# v1_circuit_EAGLE.net
KiCad netlist of a schematic drawn in EAGLE
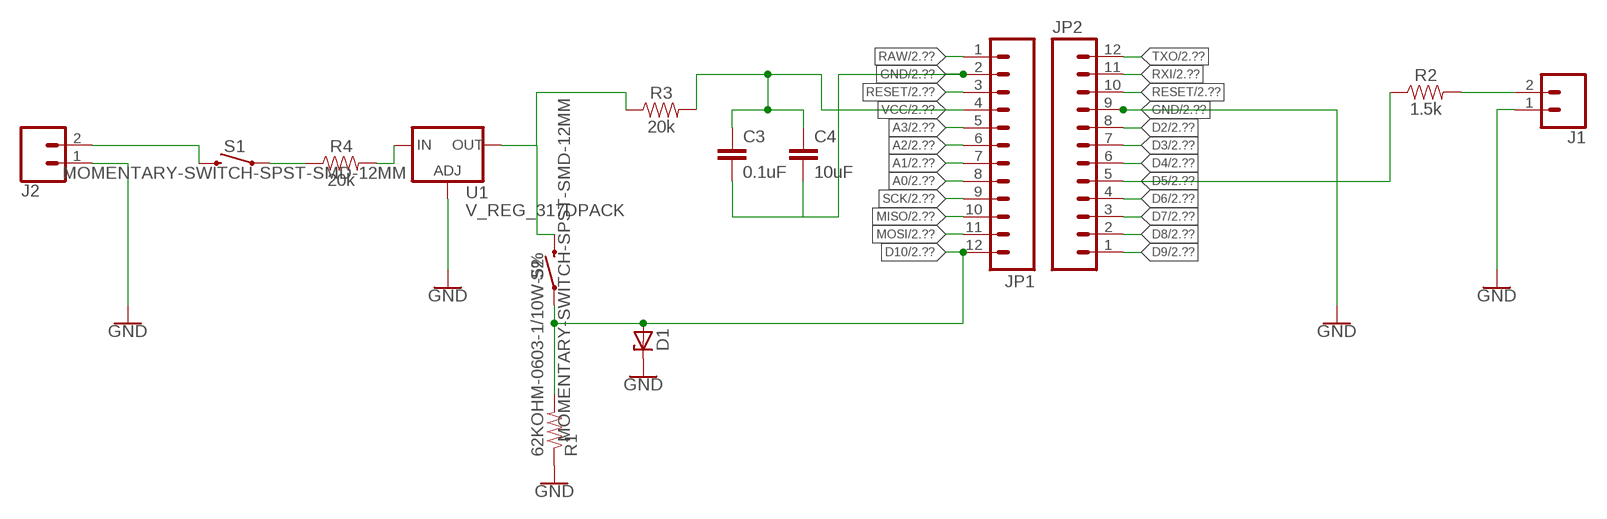
[diagram p0: schematic, sheet 1]
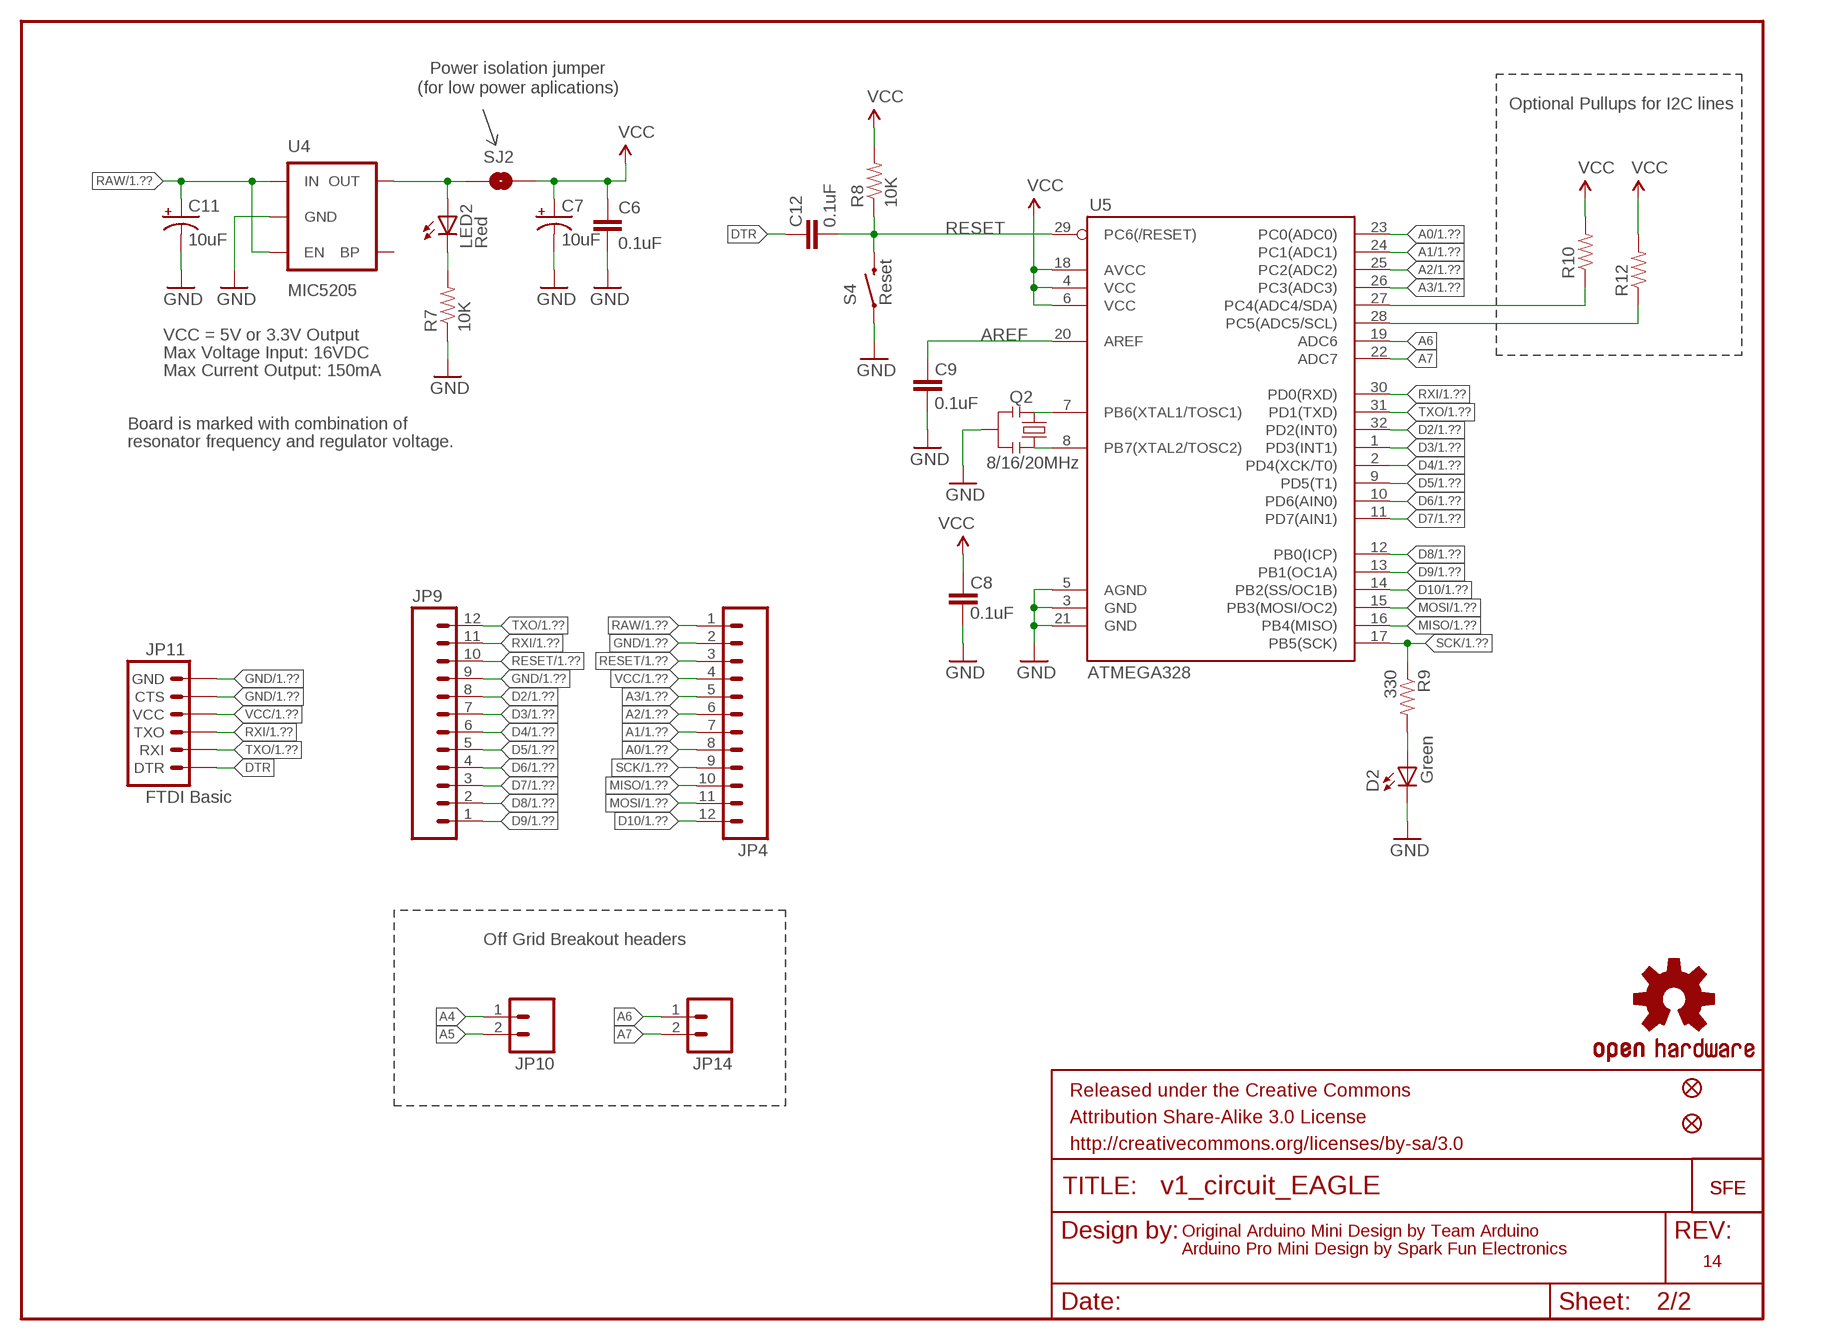
[diagram p1: schematic, sheet 2]

(export (version "E")
  (design (tool "Eeschema 10.0.6"))
  (components
    (comp (ref "C3")
      (value "0.1uF")
      (footprint "eagle-import:0603")
      (libsource (lib "eagle-import") (part "0.1UF-0603-100V-10%"))
    )
    (comp (ref "C4")
      (value "10uF")
      (footprint "eagle-import:0805")
      (libsource (lib "eagle-import") (part "10UF-0805-10V-10%"))
    )
    (comp (ref "D1")
      (value "ZENER-DIODETO236")
      (footprint "eagle-import:TO236")
      (libsource (lib "eagle-import") (part "ZENER-DIODETO236"))
    )
    (comp (ref "J1")
      (value "CONN_02-JST-2MM-SMT")
      (footprint "eagle-import:JST-2-SMD")
      (libsource (lib "eagle-import") (part "CONN_02-JST-2MM-SMT"))
    )
    (comp (ref "J2")
      (value "CONN_02-JST-2MM-SMT")
      (footprint "eagle-import:JST-2-SMD")
      (libsource (lib "eagle-import") (part "CONN_02-JST-2MM-SMT"))
    )
    (comp (ref "JP1")
      (value "M12PTH")
      (footprint "eagle-import:1X12")
      (libsource (lib "eagle-import") (part "M12PTH"))
    )
    (comp (ref "JP2")
      (value "M12PTH")
      (footprint "eagle-import:1X12")
      (libsource (lib "eagle-import") (part "M12PTH"))
    )
    (comp (ref "R1")
      (value "62KOHM-0603-1/10W-5%")
      (footprint "eagle-import:0603")
      (libsource (lib "eagle-import") (part "62KOHM-0603-1/10W-5%"))
    )
    (comp (ref "R2")
      (value "1.5k")
      (footprint "eagle-import:0603")
      (libsource (lib "eagle-import") (part "1.5KOHM-0603-1/10W-1%"))
    )
    (comp (ref "R3")
      (value "20k")
      (footprint "eagle-import:0603")
      (libsource (lib "eagle-import") (part "20KOHM-0603-1/10W-5%"))
    )
    (comp (ref "R4")
      (value "20k")
      (footprint "eagle-import:0603")
      (libsource (lib "eagle-import") (part "20KOHM-0603-1/10W-5%"))
    )
    (comp (ref "S1")
      (value "MOMENTARY-SWITCH-SPST-SMD-12MM")
      (footprint "eagle-import:TACTILE_SWITCH_SMD_12MM")
      (libsource (lib "eagle-import") (part "MOMENTARY-SWITCH-SPST-SMD-12MM"))
    )
    (comp (ref "S2")
      (value "MOMENTARY-SWITCH-SPST-SMD-12MM")
      (footprint "eagle-import:TACTILE_SWITCH_SMD_12MM")
      (libsource (lib "eagle-import") (part "MOMENTARY-SWITCH-SPST-SMD-12MM"))
    )
    (comp (ref "U1")
      (value "V_REG_317DPACK")
      (footprint "eagle-import:V-REG_DPACK")
      (libsource (lib "eagle-import") (part "V_REG_317DPACK"))
    )
    (comp (ref "C6")
      (value "0.1uF")
      (footprint "eagle-import:0603-CAP")
      (libsource (lib "eagle-import") (part "CAP0603-CAP"))
    )
    (comp (ref "C7")
      (value "10uF")
      (footprint "eagle-import:EIA3216")
      (libsource (lib "eagle-import") (part "CAP_POL1206"))
    )
    (comp (ref "C8")
      (value "0.1uF")
      (footprint "eagle-import:0603-CAP")
      (libsource (lib "eagle-import") (part "CAP0603-CAP"))
    )
    (comp (ref "C9")
      (value "0.1uF")
      (footprint "eagle-import:0603-CAP")
      (libsource (lib "eagle-import") (part "CAP0603-CAP"))
    )
    (comp (ref "C11")
      (value "10uF")
      (footprint "eagle-import:EIA3216")
      (libsource (lib "eagle-import") (part "CAP_POL1206"))
    )
    (comp (ref "C12")
      (value "0.1uF")
      (footprint "eagle-import:0603-CAP")
      (libsource (lib "eagle-import") (part "CAP0603-CAP"))
    )
    (comp (ref "D2")
      (value "Green")
      (footprint "eagle-import:0603-LED-ALT1")
      (libsource (lib "eagle-import") (part "LED"))
    )
    (comp (ref "FRAME2")
      (value "FRAME-LETTER")
      (footprint "eagle-import:CREATIVE_COMMONS")
      (libsource (lib "eagle-import") (part "FRAME-LETTER"))
    )
    (comp (ref "JP4")
      (value "M12PTH")
      (footprint "eagle-import:1X12")
      (libsource (lib "eagle-import") (part "M12PTH"))
    )
    (comp (ref "JP9")
      (value "M12PTH")
      (footprint "eagle-import:1X12")
      (libsource (lib "eagle-import") (part "M12PTH"))
    )
    (comp (ref "JP10")
      (value "M02PTH")
      (footprint "eagle-import:1X02")
      (libsource (lib "eagle-import") (part "M02PTH"))
    )
    (comp (ref "JP11")
      (value "FTDI Basic")
      (footprint "eagle-import:1X06")
      (libsource (lib "eagle-import") (part "ARDUINO_SERIAL_PROGRAMPTH"))
    )
    (comp (ref "JP12")
      (value "FIDUCIALUFIDUCIAL")
      (footprint "eagle-import:MICRO-FIDUCIAL")
      (libsource (lib "eagle-import") (part "FIDUCIALUFIDUCIAL"))
    )
    (comp (ref "JP13")
      (value "FIDUCIALUFIDUCIAL")
      (footprint "eagle-import:MICRO-FIDUCIAL")
      (libsource (lib "eagle-import") (part "FIDUCIALUFIDUCIAL"))
    )
    (comp (ref "JP14")
      (value "M02PTH")
      (footprint "eagle-import:1X02")
      (libsource (lib "eagle-import") (part "M02PTH"))
    )
    (comp (ref "LED2")
      (value "Red")
      (footprint "eagle-import:0603-LED-ALT1")
      (libsource (lib "eagle-import") (part "LED"))
    )
    (comp (ref "Q2")
      (value "8/16/20MHz")
      (footprint "eagle-import:RESONATOR-SMD-1_1")
      (libsource (lib "eagle-import") (part "RESONATOR1{colon}1"))
    )
    (comp (ref "R7")
      (value "10K")
      (footprint "eagle-import:0603-RES")
      (libsource (lib "eagle-import") (part "RESISTOR0603-RES"))
    )
    (comp (ref "R8")
      (value "10K")
      (footprint "eagle-import:0603-RES")
      (libsource (lib "eagle-import") (part "RESISTOR0603-RES"))
    )
    (comp (ref "R9")
      (value "330")
      (footprint "eagle-import:0603-RES")
      (libsource (lib "eagle-import") (part "RESISTOR0603-RES"))
    )
    (comp (ref "R10")
      (value "RESISTOR0603-RES")
      (footprint "eagle-import:0603-RES")
      (libsource (lib "eagle-import") (part "RESISTOR0603-RES"))
    )
    (comp (ref "R12")
      (value "RESISTOR0603-RES")
      (footprint "eagle-import:0603-RES")
      (libsource (lib "eagle-import") (part "RESISTOR0603-RES"))
    )
    (comp (ref "S4")
      (value "Reset")
      (footprint "eagle-import:TACTILE-SWITCH-SMD-ALT01")
      (libsource (lib "eagle-import") (part "SWITCH-MOMENTARY-2SMD-ALT01"))
    )
    (comp (ref "SJ2")
      (value "SOLDERJUMPERNC")
      (footprint "eagle-import:SJ_2S")
      (libsource (lib "eagle-import") (part "SOLDERJUMPERNC"))
    )
    (comp (ref "U$2")
      (value "LOGO-SFENEW")
      (footprint "eagle-import:SFE-NEW-WEBLOGO")
      (libsource (lib "eagle-import") (part "LOGO-SFENEW"))
    )
    (comp (ref "U$4")
      (value "LOGO-SFESK")
      (footprint "eagle-import:SFE-LOGO-FLAME")
      (libsource (lib "eagle-import") (part "LOGO-SFESK"))
    )
    (comp (ref "U$5")
      (value "OSHW-LOGOS")
      (footprint "eagle-import:OSHW-LOGO-S")
      (libsource (lib "eagle-import") (part "OSHW-LOGOS"))
    )
    (comp (ref "U4")
      (value "MIC5205")
      (footprint "eagle-import:SOT23-5")
      (libsource (lib "eagle-import") (part "V_REG_LDOSMD"))
    )
    (comp (ref "U5")
      (value "ATMEGA328")
      (footprint "eagle-import:TQFP32-08")
      (libsource (lib "eagle-import") (part "ATMEGA168"))
    )
  )
  (nets
    (net (code "1") (name "A0") (class "Default")
      (node (ref "JP1") (pin "8") (pinfunction "8_8") (pintype "passive"))
      (node (ref "JP4") (pin "8") (pinfunction "8_8") (pintype "passive"))
      (node (ref "U5") (pin "23") (pinfunction "PC0(ADC0)_23") (pintype "bidirectional"))
    )
    (net (code "2") (name "A1") (class "Default")
      (node (ref "JP1") (pin "7") (pinfunction "7_7") (pintype "passive"))
      (node (ref "JP4") (pin "7") (pinfunction "7_7") (pintype "passive"))
      (node (ref "U5") (pin "24") (pinfunction "PC1(ADC1)_24") (pintype "bidirectional"))
    )
    (net (code "3") (name "A2") (class "Default")
      (node (ref "JP1") (pin "6") (pinfunction "6_6") (pintype "passive"))
      (node (ref "JP4") (pin "6") (pinfunction "6_6") (pintype "passive"))
      (node (ref "U5") (pin "25") (pinfunction "PC2(ADC2)_25") (pintype "bidirectional"))
    )
    (net (code "4") (name "A3") (class "Default")
      (node (ref "JP1") (pin "5") (pinfunction "5_5") (pintype "passive"))
      (node (ref "JP4") (pin "5") (pinfunction "5_5") (pintype "passive"))
      (node (ref "U5") (pin "26") (pinfunction "PC3(ADC3)_26") (pintype "bidirectional"))
    )
    (net (code "5") (name "A4") (class "Default")
      (node (ref "JP10") (pin "1") (pinfunction "1_1") (pintype "passive"))
      (node (ref "R10") (pin "1") (pinfunction "1_1") (pintype "passive"))
      (node (ref "U5") (pin "27") (pinfunction "PC4(ADC4/SDA)_27") (pintype "bidirectional"))
    )
    (net (code "6") (name "A5") (class "Default")
      (node (ref "JP10") (pin "2") (pinfunction "2_2") (pintype "passive"))
      (node (ref "R12") (pin "1") (pinfunction "1_1") (pintype "passive"))
      (node (ref "U5") (pin "28") (pinfunction "PC5(ADC5/SCL)_28") (pintype "bidirectional"))
    )
    (net (code "7") (name "A6") (class "Default")
      (node (ref "JP14") (pin "1") (pinfunction "1_1") (pintype "passive"))
      (node (ref "U5") (pin "19") (pinfunction "ADC6_19") (pintype "bidirectional"))
    )
    (net (code "8") (name "A7") (class "Default")
      (node (ref "JP14") (pin "2") (pinfunction "2_2") (pintype "passive"))
      (node (ref "U5") (pin "22") (pinfunction "ADC7_22") (pintype "bidirectional"))
    )
    (net (code "9") (name "AREF") (class "Default")
      (node (ref "C9") (pin "2") (pinfunction "2_2") (pintype "passive"))
      (node (ref "U5") (pin "20") (pinfunction "AREF_20") (pintype "bidirectional"))
    )
    (net (code "10") (name "D2") (class "Default")
      (node (ref "JP2") (pin "8") (pinfunction "8_8") (pintype "passive"))
      (node (ref "JP9") (pin "8") (pinfunction "8_8") (pintype "passive"))
      (node (ref "U5") (pin "32") (pinfunction "PD2(INT0)_32") (pintype "bidirectional"))
    )
    (net (code "11") (name "D3") (class "Default")
      (node (ref "JP2") (pin "7") (pinfunction "7_7") (pintype "passive"))
      (node (ref "JP9") (pin "7") (pinfunction "7_7") (pintype "passive"))
      (node (ref "U5") (pin "1") (pinfunction "PD3(INT1)_1") (pintype "bidirectional"))
    )
    (net (code "12") (name "D4") (class "Default")
      (node (ref "JP2") (pin "6") (pinfunction "6_6") (pintype "passive"))
      (node (ref "JP9") (pin "6") (pinfunction "6_6") (pintype "passive"))
      (node (ref "U5") (pin "2") (pinfunction "PD4(XCK/T0)_2") (pintype "bidirectional"))
    )
    (net (code "13") (name "D5") (class "Default")
      (node (ref "JP2") (pin "5") (pinfunction "5_5") (pintype "passive"))
      (node (ref "JP9") (pin "5") (pinfunction "5_5") (pintype "passive"))
      (node (ref "R2") (pin "1") (pinfunction "1_1") (pintype "passive"))
      (node (ref "U5") (pin "9") (pinfunction "PD5(T1)_9") (pintype "bidirectional"))
    )
    (net (code "14") (name "D6") (class "Default")
      (node (ref "JP2") (pin "4") (pinfunction "4_4") (pintype "passive"))
      (node (ref "JP9") (pin "4") (pinfunction "4_4") (pintype "passive"))
      (node (ref "U5") (pin "10") (pinfunction "PD6(AIN0)_10") (pintype "bidirectional"))
    )
    (net (code "15") (name "D7") (class "Default")
      (node (ref "JP2") (pin "3") (pinfunction "3_3") (pintype "passive"))
      (node (ref "JP9") (pin "3") (pinfunction "3_3") (pintype "passive"))
      (node (ref "U5") (pin "11") (pinfunction "PD7(AIN1)_11") (pintype "bidirectional"))
    )
    (net (code "16") (name "D8") (class "Default")
      (node (ref "JP2") (pin "2") (pinfunction "2_2") (pintype "passive"))
      (node (ref "JP9") (pin "2") (pinfunction "2_2") (pintype "passive"))
      (node (ref "U5") (pin "12") (pinfunction "PB0(ICP)_12") (pintype "bidirectional"))
    )
    (net (code "17") (name "D9") (class "Default")
      (node (ref "JP2") (pin "1") (pinfunction "1_1") (pintype "passive"))
      (node (ref "JP9") (pin "1") (pinfunction "1_1") (pintype "passive"))
      (node (ref "U5") (pin "13") (pinfunction "PB1(OC1A)_13") (pintype "bidirectional"))
    )
    (net (code "18") (name "D10") (class "Default")
      (node (ref "D1") (pin "A") (pinfunction "A_A") (pintype "passive"))
      (node (ref "JP1") (pin "12") (pinfunction "12_12") (pintype "passive"))
      (node (ref "JP4") (pin "12") (pinfunction "12_12") (pintype "passive"))
      (node (ref "R1") (pin "2") (pinfunction "2_2") (pintype "passive"))
      (node (ref "S2") (pin "1") (pinfunction "1_1") (pintype "passive"))
      (node (ref "U5") (pin "14") (pinfunction "PB2(SS/OC1B)_14") (pintype "bidirectional"))
    )
    (net (code "19") (name "DTR") (class "Default")
      (node (ref "C12") (pin "2") (pinfunction "2_2") (pintype "passive"))
      (node (ref "JP11") (pin "1") (pinfunction "DTR_1") (pintype "passive"))
    )
    (net (code "20") (name "GND") (class "Default")
      (node (ref "C11") (pin "C") (pinfunction "-_C") (pintype "passive"))
      (node (ref "C3") (pin "2") (pinfunction "2_2") (pintype "passive"))
      (node (ref "C4") (pin "2") (pinfunction "2_2") (pintype "passive"))
      (node (ref "C6") (pin "2") (pinfunction "2_2") (pintype "passive"))
      (node (ref "C7") (pin "C") (pinfunction "-_C") (pintype "passive"))
      (node (ref "C8") (pin "1") (pinfunction "1_1") (pintype "passive"))
      (node (ref "C9") (pin "1") (pinfunction "1_1") (pintype "passive"))
      (node (ref "D1") (pin "C") (pinfunction "C_C") (pintype "passive"))
      (node (ref "D2") (pin "C") (pinfunction "C_C") (pintype "passive"))
      (node (ref "J1") (pin "1") (pinfunction "2_1") (pintype "passive"))
      (node (ref "J2") (pin "1") (pinfunction "2_1") (pintype "passive"))
      (node (ref "JP1") (pin "2") (pinfunction "2_2") (pintype "passive"))
      (node (ref "JP11") (pin "5") (pinfunction "CTS_5") (pintype "passive"))
      (node (ref "JP11") (pin "6") (pinfunction "GND_6") (pintype "passive"))
      (node (ref "JP2") (pin "9") (pinfunction "9_9") (pintype "passive"))
      (node (ref "JP4") (pin "2") (pinfunction "2_2") (pintype "passive"))
      (node (ref "JP9") (pin "9") (pinfunction "9_9") (pintype "passive"))
      (node (ref "Q2") (pin "2") (pinfunction "2_2") (pintype "passive"))
      (node (ref "R1") (pin "1") (pinfunction "1_1") (pintype "passive"))
      (node (ref "R7") (pin "1") (pinfunction "1_1") (pintype "passive"))
      (node (ref "S4") (pin "1") (pinfunction "1_1") (pintype "passive"))
      (node (ref "S4") (pin "2") (pinfunction "1_2") (pintype "passive"))
      (node (ref "U1") (pin "1") (pinfunction "ADJ_1") (pintype "input"))
      (node (ref "U4") (pin "2") (pinfunction "GND_2") (pintype "input"))
      (node (ref "U5") (pin "21") (pinfunction "GND_21") (pintype "bidirectional"))
      (node (ref "U5") (pin "3") (pinfunction "GND_3") (pintype "bidirectional"))
      (node (ref "U5") (pin "5") (pinfunction "AGND_5") (pintype "bidirectional"))
    )
    (net (code "21") (name "MISO") (class "Default")
      (node (ref "JP1") (pin "10") (pinfunction "10_10") (pintype "passive"))
      (node (ref "JP4") (pin "10") (pinfunction "10_10") (pintype "passive"))
      (node (ref "U5") (pin "16") (pinfunction "PB4(MISO)_16") (pintype "bidirectional"))
    )
    (net (code "22") (name "MOSI") (class "Default")
      (node (ref "JP1") (pin "11") (pinfunction "11_11") (pintype "passive"))
      (node (ref "JP4") (pin "11") (pinfunction "11_11") (pintype "passive"))
      (node (ref "U5") (pin "15") (pinfunction "PB3(MOSI/OC2)_15") (pintype "bidirectional"))
    )
    (net (code "23") (name "Net-(D2-PadA)") (class "Default")
      (node (ref "D2") (pin "A") (pinfunction "A_A") (pintype "passive"))
      (node (ref "R9") (pin "2") (pinfunction "2_2") (pintype "passive"))
    )
    (net (code "24") (name "Net-(J1-1)") (class "Default")
      (node (ref "J1") (pin "2") (pinfunction "1_2") (pintype "passive"))
      (node (ref "R2") (pin "2") (pinfunction "2_2") (pintype "passive"))
    )
    (net (code "25") (name "Net-(J2-1)") (class "Default")
      (node (ref "J2") (pin "2") (pinfunction "1_2") (pintype "passive"))
      (node (ref "S1") (pin "3") (pinfunction "2_3") (pintype "passive"))
    )
    (net (code "26") (name "Net-(LED2-PadC)") (class "Default")
      (node (ref "LED2") (pin "C") (pinfunction "C_C") (pintype "passive"))
      (node (ref "R7") (pin "2") (pinfunction "2_2") (pintype "passive"))
    )
    (net (code "27") (name "Net-(R4-Pad1)") (class "Default")
      (node (ref "R4") (pin "1") (pinfunction "1_1") (pintype "passive"))
      (node (ref "S1") (pin "1") (pinfunction "1_1") (pintype "passive"))
    )
    (net (code "28") (name "Net-(S2-2)") (class "Default")
      (node (ref "R3") (pin "1") (pinfunction "1_1") (pintype "passive"))
      (node (ref "S2") (pin "3") (pinfunction "2_3") (pintype "passive"))
      (node (ref "U1") (pin "4") (pinfunction "OUT_4") (pintype "output"))
    )
    (net (code "29") (name "Net-(U1-IN)") (class "Default")
      (node (ref "R4") (pin "2") (pinfunction "2_2") (pintype "passive"))
      (node (ref "U1") (pin "3") (pinfunction "IN_3") (pintype "input"))
    )
    (net (code "30") (name "Net-(U4-OUT)") (class "Default")
      (node (ref "LED2") (pin "A") (pinfunction "A_A") (pintype "passive"))
      (node (ref "SJ2") (pin "1") (pinfunction "1_1") (pintype "passive"))
      (node (ref "U4") (pin "5") (pinfunction "OUT_5") (pintype "passive"))
    )
    (net (code "31") (name "Net-(U5-PB6(XTAL1{slash}TOSC1))") (class "Default")
      (node (ref "Q2") (pin "1") (pinfunction "1_1") (pintype "passive"))
      (node (ref "U5") (pin "7") (pinfunction "PB6(XTAL1/TOSC1)_7") (pintype "bidirectional"))
    )
    (net (code "32") (name "Net-(U5-PB7(XTAL2{slash}TOSC2))") (class "Default")
      (node (ref "Q2") (pin "3") (pinfunction "3_3") (pintype "passive"))
      (node (ref "U5") (pin "8") (pinfunction "PB7(XTAL2/TOSC2)_8") (pintype "bidirectional"))
    )
    (net (code "33") (name "RAW") (class "Default")
      (node (ref "C11") (pin "A") (pinfunction "+_A") (pintype "passive"))
      (node (ref "JP1") (pin "1") (pinfunction "1_1") (pintype "passive"))
      (node (ref "JP4") (pin "1") (pinfunction "1_1") (pintype "passive"))
      (node (ref "U4") (pin "1") (pinfunction "IN_1") (pintype "input"))
      (node (ref "U4") (pin "3") (pinfunction "EN_3") (pintype "input"))
    )
    (net (code "34") (name "RESET") (class "Default")
      (node (ref "C12") (pin "1") (pinfunction "1_1") (pintype "passive"))
      (node (ref "JP1") (pin "3") (pinfunction "3_3") (pintype "passive"))
      (node (ref "JP2") (pin "10") (pinfunction "10_10") (pintype "passive"))
      (node (ref "JP4") (pin "3") (pinfunction "3_3") (pintype "passive"))
      (node (ref "JP9") (pin "10") (pinfunction "10_10") (pintype "passive"))
      (node (ref "R8") (pin "1") (pinfunction "1_1") (pintype "passive"))
      (node (ref "S4") (pin "3") (pinfunction "2_3") (pintype "passive"))
      (node (ref "S4") (pin "4") (pinfunction "2_4") (pintype "passive"))
      (node (ref "U5") (pin "29") (pinfunction "PC6(/RESET)_29") (pintype "bidirectional"))
    )
    (net (code "35") (name "RXI") (class "Default")
      (node (ref "JP11") (pin "3") (pinfunction "TXO_3") (pintype "passive"))
      (node (ref "JP2") (pin "11") (pinfunction "11_11") (pintype "passive"))
      (node (ref "JP9") (pin "11") (pinfunction "11_11") (pintype "passive"))
      (node (ref "U5") (pin "30") (pinfunction "PD0(RXD)_30") (pintype "bidirectional"))
    )
    (net (code "36") (name "SCK") (class "Default")
      (node (ref "JP1") (pin "9") (pinfunction "9_9") (pintype "passive"))
      (node (ref "JP4") (pin "9") (pinfunction "9_9") (pintype "passive"))
      (node (ref "R9") (pin "1") (pinfunction "1_1") (pintype "passive"))
      (node (ref "U5") (pin "17") (pinfunction "PB5(SCK)_17") (pintype "bidirectional"))
    )
    (net (code "37") (name "TXO") (class "Default")
      (node (ref "JP11") (pin "2") (pinfunction "RXI_2") (pintype "passive"))
      (node (ref "JP2") (pin "12") (pinfunction "12_12") (pintype "passive"))
      (node (ref "JP9") (pin "12") (pinfunction "12_12") (pintype "passive"))
      (node (ref "U5") (pin "31") (pinfunction "PD1(TXD)_31") (pintype "bidirectional"))
    )
    (net (code "38") (name "VCC") (class "Default")
      (node (ref "C3") (pin "1") (pinfunction "1_1") (pintype "passive"))
      (node (ref "C4") (pin "1") (pinfunction "1_1") (pintype "passive"))
      (node (ref "C6") (pin "1") (pinfunction "1_1") (pintype "passive"))
      (node (ref "C7") (pin "A") (pinfunction "+_A") (pintype "passive"))
      (node (ref "C8") (pin "2") (pinfunction "2_2") (pintype "passive"))
      (node (ref "JP1") (pin "4") (pinfunction "4_4") (pintype "passive"))
      (node (ref "JP11") (pin "4") (pinfunction "VCC_4") (pintype "passive"))
      (node (ref "JP4") (pin "4") (pinfunction "4_4") (pintype "passive"))
      (node (ref "R10") (pin "2") (pinfunction "2_2") (pintype "passive"))
      (node (ref "R12") (pin "2") (pinfunction "2_2") (pintype "passive"))
      (node (ref "R3") (pin "2") (pinfunction "2_2") (pintype "passive"))
      (node (ref "R8") (pin "2") (pinfunction "2_2") (pintype "passive"))
      (node (ref "SJ2") (pin "2") (pinfunction "2_2") (pintype "passive"))
      (node (ref "U5") (pin "18") (pinfunction "AVCC_18") (pintype "bidirectional"))
      (node (ref "U5") (pin "4") (pinfunction "VCC_4") (pintype "bidirectional"))
      (node (ref "U5") (pin "6") (pinfunction "VCC_6") (pintype "bidirectional"))
    )
    (net (code "39") (name "unconnected-(U4-BP-Pad4)") (class "Default")
      (node (ref "U4") (pin "4") (pinfunction "BP_4") (pintype "input"))
    )
  )
)
